# RC_lowpass.net
KiCad netlist of a schematic drawn in Altium Designer
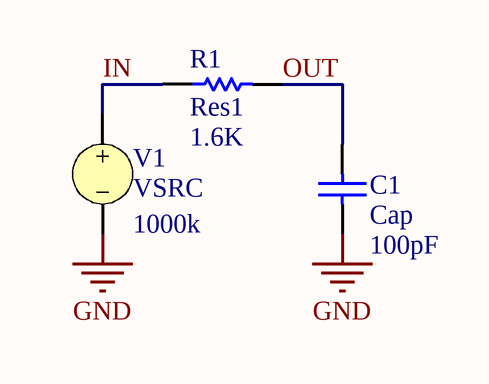
[diagram p0: RC_lowpass.SchDoc]

(export (version "E")
  (design (tool "Eeschema 10.0.6"))
  (components
    (comp (ref "C1")
      (value "Cap")
      (footprint "RAD-0.3")
      (description "Capacitor")
      (fields (field (name "ALTIUM_VALUE") "100pF") (field (name "PUBLISHER") "Altium Limited"))
      (libsource (lib "Miscellaneous Devices") (part "Cap"))
    )
    (comp (ref "R1")
      (value "Res1")
      (footprint "AXIAL-0.3")
      (description "Resistor")
      (fields (field (name "ALTIUM_VALUE") "1.6K") (field (name "PUBLISHER") "Altium Limited"))
      (libsource (lib "Miscellaneous Devices") (part "Res1"))
    )
    (comp (ref "V1")
      (value "VSRC")
      (description "Voltage Source")
      (fields (field (name "FREQUENCY") "1000k") (field (name "PUBLISHER") "Altium Limited"))
      (libsource (lib "Simulation Sources") (part "VSRC"))
    )
  )
  (nets
    (net (code "1") (name "/IN") (class "Default")
      (node (ref "R1") (pin "1") (pinfunction "1_1") (pintype "passive"))
      (node (ref "V1") (pin "1") (pinfunction "1_1") (pintype "passive"))
    )
    (net (code "2") (name "/OUT") (class "Default")
      (node (ref "C1") (pin "2") (pinfunction "2_2") (pintype "passive"))
      (node (ref "R1") (pin "2") (pinfunction "2_2") (pintype "passive"))
    )
    (net (code "3") (name "GND") (class "Default")
      (node (ref "C1") (pin "1") (pinfunction "1_1") (pintype "passive"))
      (node (ref "V1") (pin "2") (pinfunction "2_2") (pintype "passive"))
    )
  )
)
